# RSL_Satellite.net
KiCad netlist of a schematic drawn in EAGLE
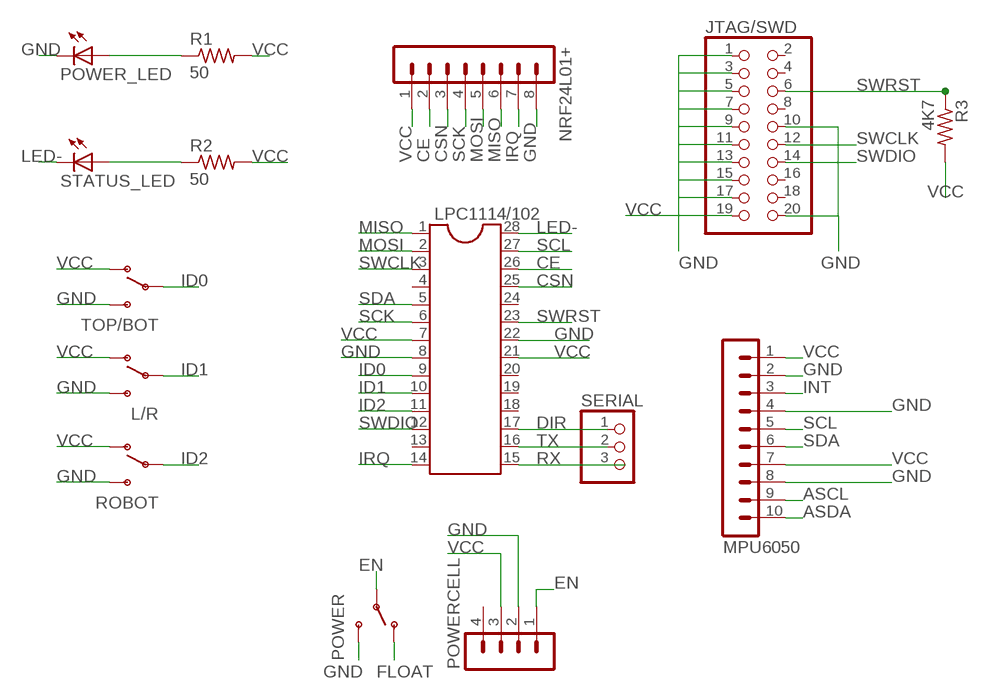
[diagram p0: schematic, sheet 1]

(export (version "E")
  (design (tool "Eeschema 10.0.6"))
  (components
    (comp (ref "JTAG/SWD")
      (value "PINHD-2X10")
      (footprint "eagle-import:2X10")
      (libsource (lib "eagle-import") (part "PINHD-2X10"))
    )
    (comp (ref "L/R")
      (value "SWITCH-SPDTPTH")
      (footprint "eagle-import:SWITCH-SPDT")
      (libsource (lib "eagle-import") (part "SWITCH-SPDTPTH"))
    )
    (comp (ref "LPC1114/102")
      (value "DIL28")
      (footprint "eagle-import:DIL28-6")
      (libsource (lib "eagle-import") (part "DIL28"))
    )
    (comp (ref "MPU6050")
      (value "MA10-1")
      (footprint "eagle-import:MA10-1")
      (libsource (lib "eagle-import") (part "MA10-1"))
    )
    (comp (ref "NRF24L01+")
      (value "MA08-1")
      (footprint "eagle-import:MA08-1")
      (libsource (lib "eagle-import") (part "MA08-1"))
    )
    (comp (ref "POWER")
      (value "SWITCH-SPDTPTH")
      (footprint "eagle-import:SWITCH-SPDT")
      (libsource (lib "eagle-import") (part "SWITCH-SPDTPTH"))
    )
    (comp (ref "POWERCELL")
      (value "MA04-1")
      (footprint "eagle-import:MA04-1")
      (libsource (lib "eagle-import") (part "MA04-1"))
    )
    (comp (ref "POWER_LED")
      (value "LED5MM")
      (footprint "eagle-import:LED5MM")
      (libsource (lib "eagle-import") (part "LED5MM"))
    )
    (comp (ref "R1")
      (value "50")
      (footprint "eagle-import:0207_10")
      (libsource (lib "eagle-import") (part "R-US_0207/10"))
    )
    (comp (ref "R2")
      (value "50")
      (footprint "eagle-import:0207_10")
      (libsource (lib "eagle-import") (part "R-US_0207/10"))
    )
    (comp (ref "R3")
      (value "4K7")
      (footprint "eagle-import:0207_10")
      (libsource (lib "eagle-import") (part "R-US_0207/10"))
    )
    (comp (ref "ROBOT")
      (value "SWITCH-SPDTPTH")
      (footprint "eagle-import:SWITCH-SPDT")
      (libsource (lib "eagle-import") (part "SWITCH-SPDTPTH"))
    )
    (comp (ref "SERIAL")
      (value "PINHD-1X3")
      (footprint "eagle-import:1X03")
      (libsource (lib "eagle-import") (part "PINHD-1X3"))
    )
    (comp (ref "STATUS_LED")
      (value "LED5MM")
      (footprint "eagle-import:LED5MM")
      (libsource (lib "eagle-import") (part "LED5MM"))
    )
    (comp (ref "TOP/BOT")
      (value "SWITCH-SPDTPTH")
      (footprint "eagle-import:SWITCH-SPDT")
      (libsource (lib "eagle-import") (part "SWITCH-SPDTPTH"))
    )
  )
  (nets
    (net (code "1") (name "/ASCL") (class "Default")
      (node (ref "MPU6050") (pin "9") (pinfunction "9_9") (pintype "passive"))
    )
    (net (code "2") (name "/ASDA") (class "Default")
      (node (ref "MPU6050") (pin "10") (pinfunction "10_10") (pintype "passive"))
    )
    (net (code "3") (name "/CE") (class "Default")
      (node (ref "LPC1114/102") (pin "26") (pinfunction "26_26") (pintype "passive"))
      (node (ref "NRF24L01+") (pin "2") (pinfunction "2_2") (pintype "passive"))
    )
    (net (code "4") (name "/CSN") (class "Default")
      (node (ref "LPC1114/102") (pin "25") (pinfunction "25_25") (pintype "passive"))
      (node (ref "NRF24L01+") (pin "3") (pinfunction "3_3") (pintype "passive"))
    )
    (net (code "5") (name "/DIR") (class "Default")
      (node (ref "LPC1114/102") (pin "17") (pinfunction "17_17") (pintype "passive"))
      (node (ref "SERIAL") (pin "1") (pinfunction "1_1") (pintype "passive"))
    )
    (net (code "6") (name "/EN") (class "Default")
      (node (ref "POWER") (pin "2") (pinfunction "P_2") (pintype "passive"))
      (node (ref "POWERCELL") (pin "1") (pinfunction "1_1") (pintype "passive"))
    )
    (net (code "7") (name "/FLOAT") (class "Default")
      (node (ref "POWER") (pin "1") (pinfunction "O_1") (pintype "passive"))
    )
    (net (code "8") (name "/GND") (class "Default")
      (node (ref "JTAG/SWD") (pin "1") (pinfunction "1_1") (pintype "passive"))
      (node (ref "JTAG/SWD") (pin "10") (pinfunction "10_10") (pintype "passive"))
      (node (ref "JTAG/SWD") (pin "11") (pinfunction "11_11") (pintype "passive"))
      (node (ref "JTAG/SWD") (pin "13") (pinfunction "13_13") (pintype "passive"))
      (node (ref "JTAG/SWD") (pin "15") (pinfunction "15_15") (pintype "passive"))
      (node (ref "JTAG/SWD") (pin "17") (pinfunction "17_17") (pintype "passive"))
      (node (ref "JTAG/SWD") (pin "20") (pinfunction "20_20") (pintype "passive"))
      (node (ref "JTAG/SWD") (pin "3") (pinfunction "3_3") (pintype "passive"))
      (node (ref "JTAG/SWD") (pin "5") (pinfunction "5_5") (pintype "passive"))
      (node (ref "JTAG/SWD") (pin "7") (pinfunction "7_7") (pintype "passive"))
      (node (ref "JTAG/SWD") (pin "9") (pinfunction "9_9") (pintype "passive"))
      (node (ref "L/R") (pin "3") (pinfunction "S_3") (pintype "passive"))
      (node (ref "LPC1114/102") (pin "22") (pinfunction "22_22") (pintype "passive"))
      (node (ref "LPC1114/102") (pin "8") (pinfunction "8_8") (pintype "passive"))
      (node (ref "MPU6050") (pin "2") (pinfunction "2_2") (pintype "passive"))
      (node (ref "MPU6050") (pin "4") (pinfunction "4_4") (pintype "passive"))
      (node (ref "MPU6050") (pin "8") (pinfunction "8_8") (pintype "passive"))
      (node (ref "NRF24L01+") (pin "8") (pinfunction "8_8") (pintype "passive"))
      (node (ref "POWER") (pin "3") (pinfunction "S_3") (pintype "passive"))
      (node (ref "POWERCELL") (pin "2") (pinfunction "2_2") (pintype "passive"))
      (node (ref "POWER_LED") (pin "K") (pinfunction "C_K") (pintype "passive"))
      (node (ref "ROBOT") (pin "3") (pinfunction "S_3") (pintype "passive"))
      (node (ref "TOP/BOT") (pin "3") (pinfunction "S_3") (pintype "passive"))
    )
    (net (code "9") (name "/ID0") (class "Default")
      (node (ref "LPC1114/102") (pin "9") (pinfunction "9_9") (pintype "passive"))
      (node (ref "TOP/BOT") (pin "2") (pinfunction "P_2") (pintype "passive"))
    )
    (net (code "10") (name "/ID1") (class "Default")
      (node (ref "L/R") (pin "2") (pinfunction "P_2") (pintype "passive"))
      (node (ref "LPC1114/102") (pin "10") (pinfunction "10_10") (pintype "passive"))
    )
    (net (code "11") (name "/ID2") (class "Default")
      (node (ref "LPC1114/102") (pin "11") (pinfunction "11_11") (pintype "passive"))
      (node (ref "ROBOT") (pin "2") (pinfunction "P_2") (pintype "passive"))
    )
    (net (code "12") (name "/INT") (class "Default")
      (node (ref "MPU6050") (pin "3") (pinfunction "3_3") (pintype "passive"))
    )
    (net (code "13") (name "/IRQ") (class "Default")
      (node (ref "LPC1114/102") (pin "14") (pinfunction "14_14") (pintype "passive"))
      (node (ref "NRF24L01+") (pin "7") (pinfunction "7_7") (pintype "passive"))
    )
    (net (code "14") (name "/LED-") (class "Default")
      (node (ref "LPC1114/102") (pin "28") (pinfunction "28_28") (pintype "passive"))
      (node (ref "STATUS_LED") (pin "K") (pinfunction "C_K") (pintype "passive"))
    )
    (net (code "15") (name "/MISO") (class "Default")
      (node (ref "LPC1114/102") (pin "1") (pinfunction "1_1") (pintype "passive"))
      (node (ref "NRF24L01+") (pin "6") (pinfunction "6_6") (pintype "passive"))
    )
    (net (code "16") (name "/MOSI") (class "Default")
      (node (ref "LPC1114/102") (pin "2") (pinfunction "2_2") (pintype "passive"))
      (node (ref "NRF24L01+") (pin "5") (pinfunction "5_5") (pintype "passive"))
    )
    (net (code "17") (name "/RX") (class "Default")
      (node (ref "LPC1114/102") (pin "15") (pinfunction "15_15") (pintype "passive"))
      (node (ref "SERIAL") (pin "3") (pinfunction "3_3") (pintype "passive"))
    )
    (net (code "18") (name "/SCK") (class "Default")
      (node (ref "LPC1114/102") (pin "6") (pinfunction "6_6") (pintype "passive"))
      (node (ref "NRF24L01+") (pin "4") (pinfunction "4_4") (pintype "passive"))
    )
    (net (code "19") (name "/SCL") (class "Default")
      (node (ref "LPC1114/102") (pin "27") (pinfunction "27_27") (pintype "passive"))
      (node (ref "MPU6050") (pin "5") (pinfunction "5_5") (pintype "passive"))
    )
    (net (code "20") (name "/SDA") (class "Default")
      (node (ref "LPC1114/102") (pin "5") (pinfunction "5_5") (pintype "passive"))
      (node (ref "MPU6050") (pin "6") (pinfunction "6_6") (pintype "passive"))
    )
    (net (code "21") (name "/SWCLK") (class "Default")
      (node (ref "JTAG/SWD") (pin "12") (pinfunction "12_12") (pintype "passive"))
      (node (ref "LPC1114/102") (pin "3") (pinfunction "3_3") (pintype "passive"))
    )
    (net (code "22") (name "/SWDIO") (class "Default")
      (node (ref "JTAG/SWD") (pin "14") (pinfunction "14_14") (pintype "passive"))
      (node (ref "LPC1114/102") (pin "12") (pinfunction "12_12") (pintype "passive"))
    )
    (net (code "23") (name "/SWRST") (class "Default")
      (node (ref "JTAG/SWD") (pin "6") (pinfunction "6_6") (pintype "passive"))
      (node (ref "LPC1114/102") (pin "23") (pinfunction "23_23") (pintype "passive"))
      (node (ref "R3") (pin "1") (pinfunction "1_1") (pintype "passive"))
    )
    (net (code "24") (name "/TX") (class "Default")
      (node (ref "LPC1114/102") (pin "16") (pinfunction "16_16") (pintype "passive"))
      (node (ref "SERIAL") (pin "2") (pinfunction "2_2") (pintype "passive"))
    )
    (net (code "25") (name "/VCC") (class "Default")
      (node (ref "JTAG/SWD") (pin "19") (pinfunction "19_19") (pintype "passive"))
      (node (ref "L/R") (pin "1") (pinfunction "O_1") (pintype "passive"))
      (node (ref "LPC1114/102") (pin "21") (pinfunction "21_21") (pintype "passive"))
      (node (ref "LPC1114/102") (pin "7") (pinfunction "7_7") (pintype "passive"))
      (node (ref "MPU6050") (pin "1") (pinfunction "1_1") (pintype "passive"))
      (node (ref "MPU6050") (pin "7") (pinfunction "7_7") (pintype "passive"))
      (node (ref "NRF24L01+") (pin "1") (pinfunction "1_1") (pintype "passive"))
      (node (ref "POWERCELL") (pin "3") (pinfunction "3_3") (pintype "passive"))
      (node (ref "R1") (pin "2") (pinfunction "2_2") (pintype "passive"))
      (node (ref "R2") (pin "2") (pinfunction "2_2") (pintype "passive"))
      (node (ref "R3") (pin "2") (pinfunction "2_2") (pintype "passive"))
      (node (ref "ROBOT") (pin "1") (pinfunction "O_1") (pintype "passive"))
      (node (ref "TOP/BOT") (pin "1") (pinfunction "O_1") (pintype "passive"))
    )
    (net (code "26") (name "Net-(POWER_LED-PadA)") (class "Default")
      (node (ref "POWER_LED") (pin "A") (pinfunction "A_A") (pintype "passive"))
      (node (ref "R1") (pin "1") (pinfunction "1_1") (pintype "passive"))
    )
    (net (code "27") (name "Net-(R2-Pad1)") (class "Default")
      (node (ref "R2") (pin "1") (pinfunction "1_1") (pintype "passive"))
      (node (ref "STATUS_LED") (pin "A") (pinfunction "A_A") (pintype "passive"))
    )
    (net (code "28") (name "unconnected-(JTAG/SWD-Pad2)") (class "Default")
      (node (ref "JTAG/SWD") (pin "2") (pinfunction "2_2") (pintype "passive"))
    )
    (net (code "29") (name "unconnected-(JTAG/SWD-Pad4)") (class "Default")
      (node (ref "JTAG/SWD") (pin "4") (pinfunction "4_4") (pintype "passive"))
    )
    (net (code "30") (name "unconnected-(JTAG/SWD-Pad8)") (class "Default")
      (node (ref "JTAG/SWD") (pin "8") (pinfunction "8_8") (pintype "passive"))
    )
    (net (code "31") (name "unconnected-(JTAG/SWD-Pad16)") (class "Default")
      (node (ref "JTAG/SWD") (pin "16") (pinfunction "16_16") (pintype "passive"))
    )
    (net (code "32") (name "unconnected-(JTAG/SWD-Pad18)") (class "Default")
      (node (ref "JTAG/SWD") (pin "18") (pinfunction "18_18") (pintype "passive"))
    )
    (net (code "33") (name "unconnected-(LPC1114/102-Pad4)") (class "Default")
      (node (ref "LPC1114/102") (pin "4") (pinfunction "4_4") (pintype "passive"))
    )
    (net (code "34") (name "unconnected-(LPC1114/102-Pad13)") (class "Default")
      (node (ref "LPC1114/102") (pin "13") (pinfunction "13_13") (pintype "passive"))
    )
    (net (code "35") (name "unconnected-(LPC1114/102-Pad18)") (class "Default")
      (node (ref "LPC1114/102") (pin "18") (pinfunction "18_18") (pintype "passive"))
    )
    (net (code "36") (name "unconnected-(LPC1114/102-Pad19)") (class "Default")
      (node (ref "LPC1114/102") (pin "19") (pinfunction "19_19") (pintype "passive"))
    )
    (net (code "37") (name "unconnected-(LPC1114/102-Pad20)") (class "Default")
      (node (ref "LPC1114/102") (pin "20") (pinfunction "20_20") (pintype "passive"))
    )
    (net (code "38") (name "unconnected-(LPC1114/102-Pad24)") (class "Default")
      (node (ref "LPC1114/102") (pin "24") (pinfunction "24_24") (pintype "passive"))
    )
    (net (code "39") (name "unconnected-(POWERCELL-Pad4)") (class "Default")
      (node (ref "POWERCELL") (pin "4") (pinfunction "4_4") (pintype "passive"))
    )
  )
)
